# ProPrj_741_2025-12-09.net
KiCad netlist of a schematic drawn in EasyEDA Pro
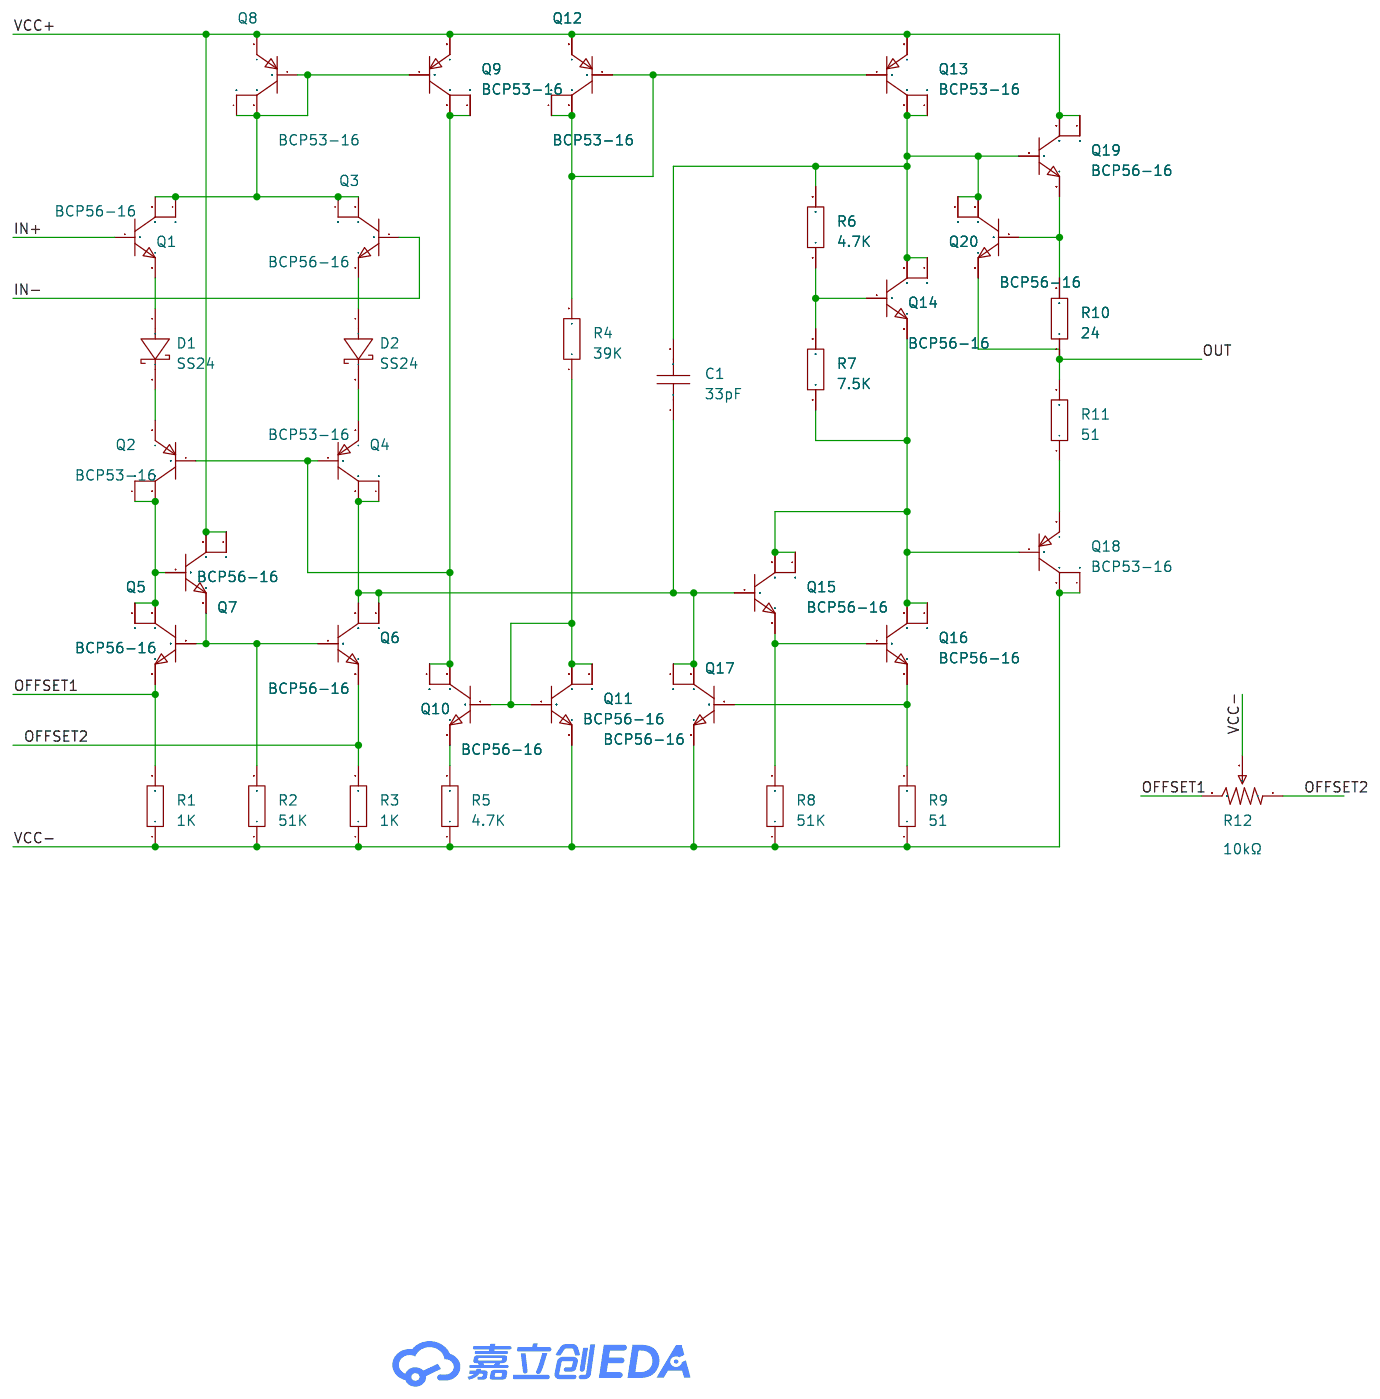
[diagram p0: schematic sheet]

(export (version "E")
  (design (tool "Eeschema 10.0.6"))
  (components
    (comp (ref "C1")
      (value "33pF")
      (footprint "easyedapro:C0805")
      (libsource (lib "easyedapro") (part "Capacitance"))
    )
    (comp (ref "D1")
      (value "SS24")
      (footprint "easyedapro:SMA_L4.3-W2.6-LS5.0-FD")
      (description "二极管配置:独立式;正向压降(Vf):550mV@2A;直流反向耐压(Vr):40V;整流电流:2A;")
      (fields (field (name "Manufacturer") "R+O(宏嘉诚)"))
      (libsource (lib "easyedapro") (part "SS24_C7420362"))
    )
    (comp (ref "D2")
      (value "SS24")
      (footprint "easyedapro:SMA_L4.3-W2.6-LS5.0-FD")
      (description "二极管配置:独立式;正向压降(Vf):550mV@2A;直流反向耐压(Vr):40V;整流电流:2A;")
      (fields (field (name "Manufacturer") "R+O(宏嘉诚)"))
      (libsource (lib "easyedapro") (part "SS24_C7420362"))
    )
    (comp (ref "Q1")
      (value "BCP56-16")
      (footprint "easyedapro:SOT-223-4_L6.5-W3.5-P2.30-LS7.0-BR")
      (description "晶体管类型:NPN;集电极电流(Ic):1A;集射极击穿电压(Vceo):80V;耗散功率(Pd):1.33W;直流电流增益(hFE):25@5mA,2V;")
      (fields (field (name "Manufacturer") "R+O(宏嘉诚)"))
      (libsource (lib "easyedapro") (part "BCP56-16_C41375109"))
    )
    (comp (ref "Q2")
      (value "BCP53-16")
      (footprint "easyedapro:SOT-223-3_L6.7-W3.7-P2.30-LS7.0-BR")
      (description "晶体管类型:PNP;集电极电流(Ic):1A;集射极击穿电压(Vceo):100V;耗散功率(Pd):1.5W;直流电流增益(hFE):250@150mA,3V;")
      (fields (field (name "Manufacturer") "R+O(宏嘉诚)"))
      (libsource (lib "easyedapro") (part "BCP53-16_C41375110"))
    )
    (comp (ref "Q3")
      (value "BCP56-16")
      (footprint "easyedapro:SOT-223-4_L6.5-W3.5-P2.30-LS7.0-BR")
      (description "晶体管类型:NPN;集电极电流(Ic):1A;集射极击穿电压(Vceo):80V;耗散功率(Pd):1.33W;直流电流增益(hFE):25@5mA,2V;")
      (fields (field (name "Manufacturer") "R+O(宏嘉诚)"))
      (libsource (lib "easyedapro") (part "BCP56-16_C41375109"))
    )
    (comp (ref "Q4")
      (value "BCP53-16")
      (footprint "easyedapro:SOT-223-3_L6.7-W3.7-P2.30-LS7.0-BR")
      (description "晶体管类型:PNP;集电极电流(Ic):1A;集射极击穿电压(Vceo):100V;耗散功率(Pd):1.5W;直流电流增益(hFE):250@150mA,3V;")
      (fields (field (name "Manufacturer") "R+O(宏嘉诚)"))
      (libsource (lib "easyedapro") (part "BCP53-16_C41375110"))
    )
    (comp (ref "Q5")
      (value "BCP56-16")
      (footprint "easyedapro:SOT-223-4_L6.5-W3.5-P2.30-LS7.0-BR")
      (description "晶体管类型:NPN;集电极电流(Ic):1A;集射极击穿电压(Vceo):80V;耗散功率(Pd):1.33W;直流电流增益(hFE):25@5mA,2V;")
      (fields (field (name "Manufacturer") "R+O(宏嘉诚)"))
      (libsource (lib "easyedapro") (part "BCP56-16_C41375109"))
    )
    (comp (ref "Q6")
      (value "BCP56-16")
      (footprint "easyedapro:SOT-223-4_L6.5-W3.5-P2.30-LS7.0-BR")
      (description "晶体管类型:NPN;集电极电流(Ic):1A;集射极击穿电压(Vceo):80V;耗散功率(Pd):1.33W;直流电流增益(hFE):25@5mA,2V;")
      (fields (field (name "Manufacturer") "R+O(宏嘉诚)"))
      (libsource (lib "easyedapro") (part "BCP56-16_C41375109"))
    )
    (comp (ref "Q7")
      (value "BCP56-16")
      (footprint "easyedapro:SOT-223-4_L6.5-W3.5-P2.30-LS7.0-BR")
      (description "晶体管类型:NPN;集电极电流(Ic):1A;集射极击穿电压(Vceo):80V;耗散功率(Pd):1.33W;直流电流增益(hFE):25@5mA,2V;")
      (fields (field (name "Manufacturer") "R+O(宏嘉诚)"))
      (libsource (lib "easyedapro") (part "BCP56-16_C41375109"))
    )
    (comp (ref "Q8")
      (value "BCP53-16")
      (footprint "easyedapro:SOT-223-3_L6.7-W3.7-P2.30-LS7.0-BR")
      (description "晶体管类型:PNP;集电极电流(Ic):1A;集射极击穿电压(Vceo):100V;耗散功率(Pd):1.5W;直流电流增益(hFE):250@150mA,3V;")
      (fields (field (name "Manufacturer") "R+O(宏嘉诚)"))
      (libsource (lib "easyedapro") (part "BCP53-16_C41375110"))
    )
    (comp (ref "Q9")
      (value "BCP53-16")
      (footprint "easyedapro:SOT-223-3_L6.7-W3.7-P2.30-LS7.0-BR")
      (description "晶体管类型:PNP;集电极电流(Ic):1A;集射极击穿电压(Vceo):100V;耗散功率(Pd):1.5W;直流电流增益(hFE):250@150mA,3V;")
      (fields (field (name "Manufacturer") "R+O(宏嘉诚)"))
      (libsource (lib "easyedapro") (part "BCP53-16_C41375110"))
    )
    (comp (ref "Q10")
      (value "BCP56-16")
      (footprint "easyedapro:SOT-223-4_L6.5-W3.5-P2.30-LS7.0-BR")
      (description "晶体管类型:NPN;集电极电流(Ic):1A;集射极击穿电压(Vceo):80V;耗散功率(Pd):1.33W;直流电流增益(hFE):25@5mA,2V;")
      (fields (field (name "Manufacturer") "R+O(宏嘉诚)"))
      (libsource (lib "easyedapro") (part "BCP56-16_C41375109"))
    )
    (comp (ref "Q11")
      (value "BCP56-16")
      (footprint "easyedapro:SOT-223-4_L6.5-W3.5-P2.30-LS7.0-BR")
      (description "晶体管类型:NPN;集电极电流(Ic):1A;集射极击穿电压(Vceo):80V;耗散功率(Pd):1.33W;直流电流增益(hFE):25@5mA,2V;")
      (fields (field (name "Manufacturer") "R+O(宏嘉诚)"))
      (libsource (lib "easyedapro") (part "BCP56-16_C41375109"))
    )
    (comp (ref "Q12")
      (value "BCP53-16")
      (footprint "easyedapro:SOT-223-3_L6.7-W3.7-P2.30-LS7.0-BR")
      (description "晶体管类型:PNP;集电极电流(Ic):1A;集射极击穿电压(Vceo):100V;耗散功率(Pd):1.5W;直流电流增益(hFE):250@150mA,3V;")
      (fields (field (name "Manufacturer") "R+O(宏嘉诚)"))
      (libsource (lib "easyedapro") (part "BCP53-16_C41375110"))
    )
    (comp (ref "Q13")
      (value "BCP53-16")
      (footprint "easyedapro:SOT-223-3_L6.7-W3.7-P2.30-LS7.0-BR")
      (description "晶体管类型:PNP;集电极电流(Ic):1A;集射极击穿电压(Vceo):100V;耗散功率(Pd):1.5W;直流电流增益(hFE):250@150mA,3V;")
      (fields (field (name "Manufacturer") "R+O(宏嘉诚)"))
      (libsource (lib "easyedapro") (part "BCP53-16_C41375110"))
    )
    (comp (ref "Q14")
      (value "BCP56-16")
      (footprint "easyedapro:SOT-223-4_L6.5-W3.5-P2.30-LS7.0-BR")
      (description "晶体管类型:NPN;集电极电流(Ic):1A;集射极击穿电压(Vceo):80V;耗散功率(Pd):1.33W;直流电流增益(hFE):25@5mA,2V;")
      (fields (field (name "Manufacturer") "R+O(宏嘉诚)"))
      (libsource (lib "easyedapro") (part "BCP56-16_C41375109"))
    )
    (comp (ref "Q15")
      (value "BCP56-16")
      (footprint "easyedapro:SOT-223-4_L6.5-W3.5-P2.30-LS7.0-BR")
      (description "晶体管类型:NPN;集电极电流(Ic):1A;集射极击穿电压(Vceo):80V;耗散功率(Pd):1.33W;直流电流增益(hFE):25@5mA,2V;")
      (fields (field (name "Manufacturer") "R+O(宏嘉诚)"))
      (libsource (lib "easyedapro") (part "BCP56-16_C41375109"))
    )
    (comp (ref "Q16")
      (value "BCP56-16")
      (footprint "easyedapro:SOT-223-4_L6.5-W3.5-P2.30-LS7.0-BR")
      (description "晶体管类型:NPN;集电极电流(Ic):1A;集射极击穿电压(Vceo):80V;耗散功率(Pd):1.33W;直流电流增益(hFE):25@5mA,2V;")
      (fields (field (name "Manufacturer") "R+O(宏嘉诚)"))
      (libsource (lib "easyedapro") (part "BCP56-16_C41375109"))
    )
    (comp (ref "Q17")
      (value "BCP56-16")
      (footprint "easyedapro:SOT-223-4_L6.5-W3.5-P2.30-LS7.0-BR")
      (description "晶体管类型:NPN;集电极电流(Ic):1A;集射极击穿电压(Vceo):80V;耗散功率(Pd):1.33W;直流电流增益(hFE):25@5mA,2V;")
      (fields (field (name "Manufacturer") "R+O(宏嘉诚)"))
      (libsource (lib "easyedapro") (part "BCP56-16_C41375109"))
    )
    (comp (ref "Q18")
      (value "BCP53-16")
      (footprint "easyedapro:SOT-223-3_L6.7-W3.7-P2.30-LS7.0-BR")
      (description "晶体管类型:PNP;集电极电流(Ic):1A;集射极击穿电压(Vceo):100V;耗散功率(Pd):1.5W;直流电流增益(hFE):250@150mA,3V;")
      (fields (field (name "Manufacturer") "R+O(宏嘉诚)"))
      (libsource (lib "easyedapro") (part "BCP53-16_C41375110"))
    )
    (comp (ref "Q19")
      (value "BCP56-16")
      (footprint "easyedapro:SOT-223-4_L6.5-W3.5-P2.30-LS7.0-BR")
      (description "晶体管类型:NPN;集电极电流(Ic):1A;集射极击穿电压(Vceo):80V;耗散功率(Pd):1.33W;直流电流增益(hFE):25@5mA,2V;")
      (fields (field (name "Manufacturer") "R+O(宏嘉诚)"))
      (libsource (lib "easyedapro") (part "BCP56-16_C41375109"))
    )
    (comp (ref "Q20")
      (value "BCP56-16")
      (footprint "easyedapro:SOT-223-4_L6.5-W3.5-P2.30-LS7.0-BR")
      (description "晶体管类型:NPN;集电极电流(Ic):1A;集射极击穿电压(Vceo):80V;耗散功率(Pd):1.33W;直流电流增益(hFE):25@5mA,2V;")
      (fields (field (name "Manufacturer") "R+O(宏嘉诚)"))
      (libsource (lib "easyedapro") (part "BCP56-16_C41375109"))
    )
    (comp (ref "R1") (value "1K") (footprint "easyedapro:R0805") (libsource (lib "easyedapro") (part "电阻")))
    (comp (ref "R2") (value "51K") (footprint "easyedapro:R0805") (libsource (lib "easyedapro") (part "电阻")))
    (comp (ref "R3") (value "1K") (footprint "easyedapro:R0805") (libsource (lib "easyedapro") (part "电阻")))
    (comp (ref "R4") (value "39K") (footprint "easyedapro:R0805") (libsource (lib "easyedapro") (part "电阻")))
    (comp (ref "R5") (value "4.7K") (footprint "easyedapro:R0805") (libsource (lib "easyedapro") (part "电阻")))
    (comp (ref "R6") (value "4.7K") (footprint "easyedapro:R0805") (libsource (lib "easyedapro") (part "电阻")))
    (comp (ref "R7") (value "7.5K") (footprint "easyedapro:R0805") (libsource (lib "easyedapro") (part "电阻")))
    (comp (ref "R8") (value "51K") (footprint "easyedapro:R0805") (libsource (lib "easyedapro") (part "电阻")))
    (comp (ref "R9") (value "51") (footprint "easyedapro:R0805") (libsource (lib "easyedapro") (part "电阻")))
    (comp (ref "R10") (value "24") (footprint "easyedapro:R0805") (libsource (lib "easyedapro") (part "电阻")))
    (comp (ref "R11") (value "51") (footprint "easyedapro:R0805") (libsource (lib "easyedapro") (part "电阻")))
    (comp (ref "R12")
      (value "10kΩ")
      (footprint "easyedapro:RES-ADJ-TH_3296W")
      (description "阻值:10kΩ;精度:±10%;功率:500mW;温度系数:±250ppm/°C;")
      (fields (field (name "Manufacturer Part") "3296W-1-103") (field (name "Manufacturer") "JIERR(捷而瑞)"))
      (libsource (lib "easyedapro") (part "3296W-1-103_C48997937"))
    )
  )
  (nets
    (net (code "1") (name "/IN+") (class "Default")
      (node (ref "Q1") (pin "1") (pinfunction "B_1") (pintype "input"))
    )
    (net (code "2") (name "/IN-") (class "Default")
      (node (ref "Q3") (pin "1") (pinfunction "B_1") (pintype "input"))
    )
    (net (code "3") (name "/OFFSET1") (class "Default")
      (node (ref "Q5") (pin "3") (pinfunction "E_3") (pintype "input"))
      (node (ref "R1") (pin "2") (pinfunction "2_2") (pintype "input"))
      (node (ref "R12") (pin "3") (pinfunction "3_3") (pintype "unspecified"))
    )
    (net (code "4") (name "/OFFSET2") (class "Default")
      (node (ref "Q6") (pin "3") (pinfunction "E_3") (pintype "input"))
      (node (ref "R12") (pin "1") (pinfunction "1_1") (pintype "unspecified"))
      (node (ref "R3") (pin "2") (pinfunction "2_2") (pintype "input"))
    )
    (net (code "5") (name "/OUT") (class "Default")
      (node (ref "Q20") (pin "3") (pinfunction "E_3") (pintype "input"))
      (node (ref "R10") (pin "1") (pinfunction "1_1") (pintype "input"))
      (node (ref "R11") (pin "2") (pinfunction "2_2") (pintype "input"))
    )
    (net (code "6") (name "/VCC+") (class "Default")
      (node (ref "Q12") (pin "3") (pinfunction "E_3") (pintype "input"))
      (node (ref "Q13") (pin "3") (pinfunction "E_3") (pintype "input"))
      (node (ref "Q19") (pin "2") (pinfunction "C_2") (pintype "input"))
      (node (ref "Q19") (pin "4") (pinfunction "C_4") (pintype "input"))
      (node (ref "Q7") (pin "2") (pinfunction "C_2") (pintype "input"))
      (node (ref "Q7") (pin "4") (pinfunction "C_4") (pintype "input"))
      (node (ref "Q8") (pin "3") (pinfunction "E_3") (pintype "input"))
      (node (ref "Q9") (pin "3") (pinfunction "E_3") (pintype "input"))
    )
    (net (code "7") (name "/VCC-") (class "Default")
      (node (ref "Q11") (pin "3") (pinfunction "E_3") (pintype "input"))
      (node (ref "Q17") (pin "3") (pinfunction "E_3") (pintype "input"))
      (node (ref "Q18") (pin "2") (pinfunction "C_2") (pintype "input"))
      (node (ref "Q18") (pin "4") (pinfunction "C_4") (pintype "input"))
      (node (ref "R1") (pin "1") (pinfunction "1_1") (pintype "input"))
      (node (ref "R12") (pin "2") (pinfunction "2_2") (pintype "unspecified"))
      (node (ref "R2") (pin "1") (pinfunction "1_1") (pintype "input"))
      (node (ref "R3") (pin "1") (pinfunction "1_1") (pintype "input"))
      (node (ref "R5") (pin "1") (pinfunction "1_1") (pintype "input"))
      (node (ref "R8") (pin "1") (pinfunction "1_1") (pintype "input"))
      (node (ref "R9") (pin "1") (pinfunction "1_1") (pintype "input"))
    )
    (net (code "8") (name "Net-(D1-A)") (class "Default")
      (node (ref "D1") (pin "1") (pinfunction "A_1") (pintype "unspecified"))
      (node (ref "Q1") (pin "3") (pinfunction "E_3") (pintype "input"))
    )
    (net (code "9") (name "Net-(D1-K)") (class "Default")
      (node (ref "D1") (pin "2") (pinfunction "K_2") (pintype "unspecified"))
      (node (ref "Q2") (pin "3") (pinfunction "E_3") (pintype "input"))
    )
    (net (code "10") (name "Net-(D2-A)") (class "Default")
      (node (ref "D2") (pin "1") (pinfunction "A_1") (pintype "unspecified"))
      (node (ref "Q3") (pin "3") (pinfunction "E_3") (pintype "input"))
    )
    (net (code "11") (name "Net-(D2-K)") (class "Default")
      (node (ref "D2") (pin "2") (pinfunction "K_2") (pintype "unspecified"))
      (node (ref "Q4") (pin "3") (pinfunction "E_3") (pintype "input"))
    )
    (net (code "12") (name "Net-(Q2-B)") (class "Default")
      (node (ref "Q10") (pin "2") (pinfunction "C_2") (pintype "input"))
      (node (ref "Q10") (pin "4") (pinfunction "C_4") (pintype "input"))
      (node (ref "Q2") (pin "1") (pinfunction "B_1") (pintype "input"))
      (node (ref "Q4") (pin "1") (pinfunction "B_1") (pintype "input"))
      (node (ref "Q9") (pin "2") (pinfunction "C_2") (pintype "input"))
      (node (ref "Q9") (pin "4") (pinfunction "C_4") (pintype "input"))
    )
    (net (code "13") (name "Net-(Q5-B)") (class "Default")
      (node (ref "Q5") (pin "1") (pinfunction "B_1") (pintype "input"))
      (node (ref "Q6") (pin "1") (pinfunction "B_1") (pintype "input"))
      (node (ref "Q7") (pin "3") (pinfunction "E_3") (pintype "input"))
      (node (ref "R2") (pin "2") (pinfunction "2_2") (pintype "input"))
    )
    (net (code "14") (name "Net-(Q7-B)") (class "Default")
      (node (ref "Q2") (pin "2") (pinfunction "C_2") (pintype "input"))
      (node (ref "Q2") (pin "4") (pinfunction "C_4") (pintype "input"))
      (node (ref "Q5") (pin "2") (pinfunction "C_2") (pintype "input"))
      (node (ref "Q5") (pin "4") (pinfunction "C_4") (pintype "input"))
      (node (ref "Q7") (pin "1") (pinfunction "B_1") (pintype "input"))
    )
    (net (code "15") (name "Net-(Q8-B)") (class "Default")
      (node (ref "Q1") (pin "2") (pinfunction "C_2") (pintype "input"))
      (node (ref "Q1") (pin "4") (pinfunction "C_4") (pintype "input"))
      (node (ref "Q3") (pin "2") (pinfunction "C_2") (pintype "input"))
      (node (ref "Q3") (pin "4") (pinfunction "C_4") (pintype "input"))
      (node (ref "Q8") (pin "1") (pinfunction "B_1") (pintype "input"))
      (node (ref "Q8") (pin "2") (pinfunction "C_2") (pintype "input"))
      (node (ref "Q8") (pin "4") (pinfunction "C_4") (pintype "input"))
      (node (ref "Q9") (pin "1") (pinfunction "B_1") (pintype "input"))
    )
    (net (code "16") (name "Net-(Q10-B)") (class "Default")
      (node (ref "Q10") (pin "1") (pinfunction "B_1") (pintype "input"))
      (node (ref "Q11") (pin "1") (pinfunction "B_1") (pintype "input"))
      (node (ref "Q11") (pin "2") (pinfunction "C_2") (pintype "input"))
      (node (ref "Q11") (pin "4") (pinfunction "C_4") (pintype "input"))
      (node (ref "R4") (pin "1") (pinfunction "1_1") (pintype "input"))
    )
    (net (code "17") (name "Net-(Q10-E)") (class "Default")
      (node (ref "Q10") (pin "3") (pinfunction "E_3") (pintype "input"))
      (node (ref "R5") (pin "2") (pinfunction "2_2") (pintype "input"))
    )
    (net (code "18") (name "Net-(Q12-B)") (class "Default")
      (node (ref "Q12") (pin "1") (pinfunction "B_1") (pintype "input"))
      (node (ref "Q12") (pin "2") (pinfunction "C_2") (pintype "input"))
      (node (ref "Q12") (pin "4") (pinfunction "C_4") (pintype "input"))
      (node (ref "Q13") (pin "1") (pinfunction "B_1") (pintype "input"))
      (node (ref "R4") (pin "2") (pinfunction "2_2") (pintype "input"))
    )
    (net (code "19") (name "Net-(Q14-B)") (class "Default")
      (node (ref "Q14") (pin "1") (pinfunction "B_1") (pintype "input"))
      (node (ref "R6") (pin "1") (pinfunction "1_1") (pintype "input"))
      (node (ref "R7") (pin "2") (pinfunction "2_2") (pintype "input"))
    )
    (net (code "20") (name "Net-(Q14-E)") (class "Default")
      (node (ref "Q14") (pin "3") (pinfunction "E_3") (pintype "input"))
      (node (ref "Q15") (pin "2") (pinfunction "C_2") (pintype "input"))
      (node (ref "Q15") (pin "4") (pinfunction "C_4") (pintype "input"))
      (node (ref "Q16") (pin "2") (pinfunction "C_2") (pintype "input"))
      (node (ref "Q16") (pin "4") (pinfunction "C_4") (pintype "input"))
      (node (ref "Q18") (pin "1") (pinfunction "B_1") (pintype "input"))
      (node (ref "R7") (pin "1") (pinfunction "1_1") (pintype "input"))
    )
    (net (code "21") (name "Net-(Q15-B)") (class "Default")
      (node (ref "C1") (pin "1") (pinfunction "1_1") (pintype "input"))
      (node (ref "Q15") (pin "1") (pinfunction "B_1") (pintype "input"))
      (node (ref "Q17") (pin "2") (pinfunction "C_2") (pintype "input"))
      (node (ref "Q17") (pin "4") (pinfunction "C_4") (pintype "input"))
      (node (ref "Q4") (pin "2") (pinfunction "C_2") (pintype "input"))
      (node (ref "Q4") (pin "4") (pinfunction "C_4") (pintype "input"))
      (node (ref "Q6") (pin "2") (pinfunction "C_2") (pintype "input"))
      (node (ref "Q6") (pin "4") (pinfunction "C_4") (pintype "input"))
    )
    (net (code "22") (name "Net-(Q15-E)") (class "Default")
      (node (ref "Q15") (pin "3") (pinfunction "E_3") (pintype "input"))
      (node (ref "Q16") (pin "1") (pinfunction "B_1") (pintype "input"))
      (node (ref "R8") (pin "2") (pinfunction "2_2") (pintype "input"))
    )
    (net (code "23") (name "Net-(Q16-E)") (class "Default")
      (node (ref "Q16") (pin "3") (pinfunction "E_3") (pintype "input"))
      (node (ref "Q17") (pin "1") (pinfunction "B_1") (pintype "input"))
      (node (ref "R9") (pin "2") (pinfunction "2_2") (pintype "input"))
    )
    (net (code "24") (name "Net-(Q18-E)") (class "Default")
      (node (ref "Q18") (pin "3") (pinfunction "E_3") (pintype "input"))
      (node (ref "R11") (pin "1") (pinfunction "1_1") (pintype "input"))
    )
    (net (code "25") (name "Net-(Q19-B)") (class "Default")
      (node (ref "C1") (pin "2") (pinfunction "2_2") (pintype "input"))
      (node (ref "Q13") (pin "2") (pinfunction "C_2") (pintype "input"))
      (node (ref "Q13") (pin "4") (pinfunction "C_4") (pintype "input"))
      (node (ref "Q14") (pin "2") (pinfunction "C_2") (pintype "input"))
      (node (ref "Q14") (pin "4") (pinfunction "C_4") (pintype "input"))
      (node (ref "Q19") (pin "1") (pinfunction "B_1") (pintype "input"))
      (node (ref "Q20") (pin "2") (pinfunction "C_2") (pintype "input"))
      (node (ref "Q20") (pin "4") (pinfunction "C_4") (pintype "input"))
      (node (ref "R6") (pin "2") (pinfunction "2_2") (pintype "input"))
    )
    (net (code "26") (name "Net-(Q19-E)") (class "Default")
      (node (ref "Q19") (pin "3") (pinfunction "E_3") (pintype "input"))
      (node (ref "Q20") (pin "1") (pinfunction "B_1") (pintype "input"))
      (node (ref "R10") (pin "2") (pinfunction "2_2") (pintype "input"))
    )
  )
)
